# LedDisplay.net
KiCad netlist of a schematic drawn in EAGLE
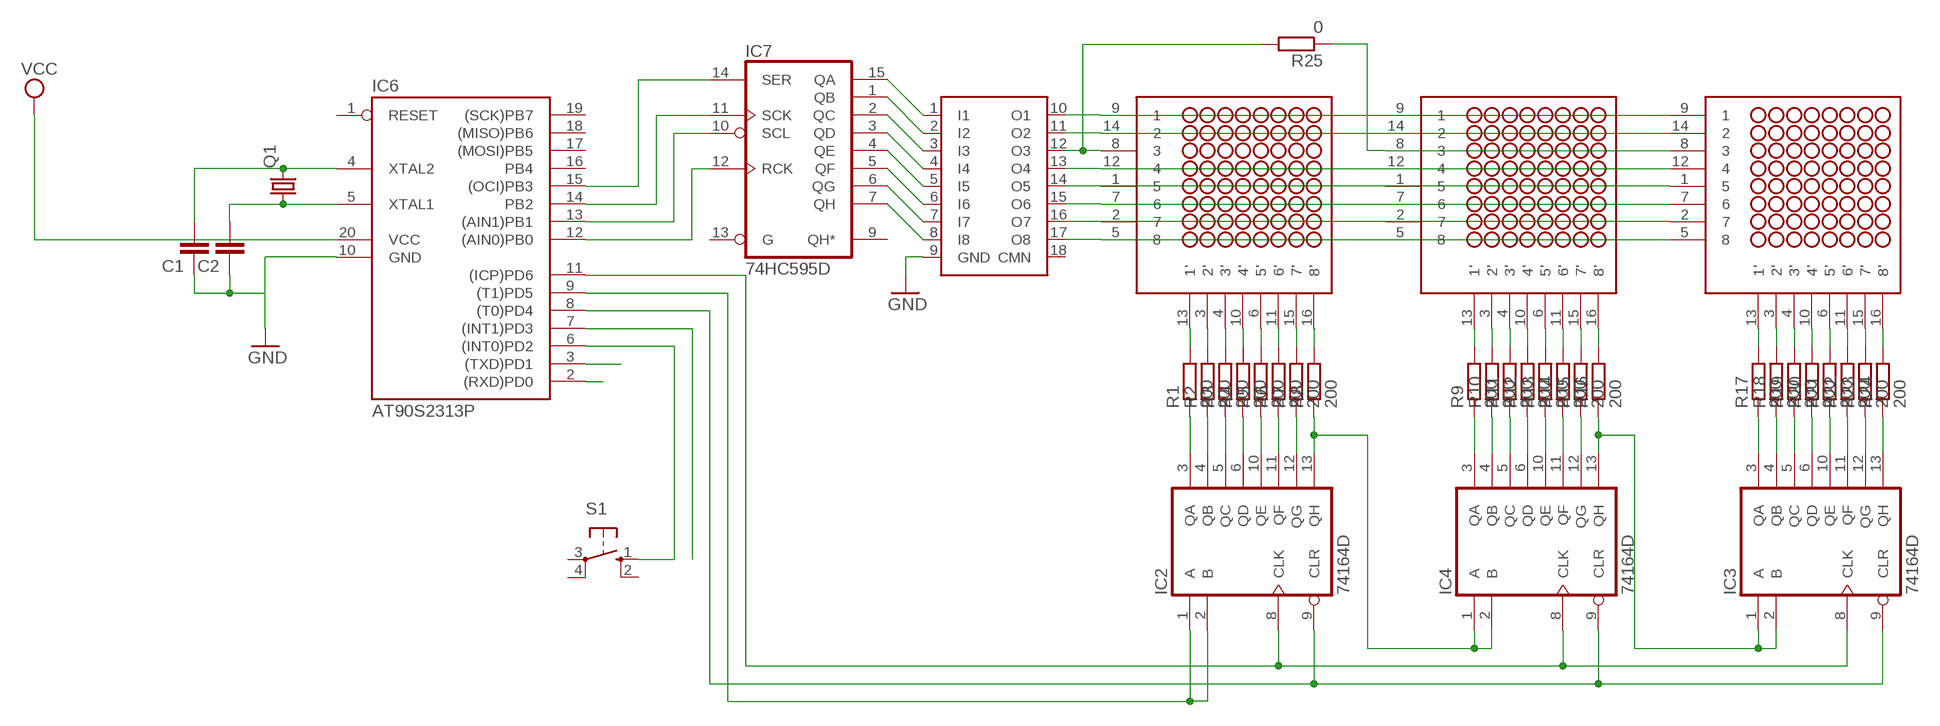
[diagram p0: schematic, sheet 1]

(export (version "E")
  (design (tool "Eeschema 10.0.6"))
  (components
    (comp (ref "C1")
      (value "C2,5-3")
      (footprint "eagle-import:C2.5-3")
      (libsource (lib "eagle-import") (part "C2,5-3"))
    )
    (comp (ref "C2")
      (value "C2,5-3")
      (footprint "eagle-import:C2.5-3")
      (libsource (lib "eagle-import") (part "C2,5-3"))
    )
    (comp (ref "IC2")
      (value "74164D")
      (footprint "eagle-import:SO14")
      (libsource (lib "eagle-import") (part "74164D"))
    )
    (comp (ref "IC3")
      (value "74164D")
      (footprint "eagle-import:SO14")
      (libsource (lib "eagle-import") (part "74164D"))
    )
    (comp (ref "IC4")
      (value "74164D")
      (footprint "eagle-import:SO14")
      (libsource (lib "eagle-import") (part "74164D"))
    )
    (comp (ref "IC6")
      (value "AT90S2313P")
      (footprint "eagle-import:DIL20")
      (libsource (lib "eagle-import") (part "AT90S2313P"))
    )
    (comp (ref "IC7")
      (value "74HC595D")
      (footprint "eagle-import:SO16")
      (libsource (lib "eagle-import") (part "74595DHC"))
    )
    (comp (ref "Q1")
      (value "CRYSTALHC49U70")
      (footprint "eagle-import:HC49U70")
      (libsource (lib "eagle-import") (part "CRYSTALHC49U70"))
    )
    (comp (ref "R1")
      (value "200")
      (footprint "eagle-import:M1206")
      (libsource (lib "eagle-import") (part "R-EU_M1206"))
    )
    (comp (ref "R2")
      (value "200")
      (footprint "eagle-import:M1206")
      (libsource (lib "eagle-import") (part "R-EU_M1206"))
    )
    (comp (ref "R3")
      (value "200")
      (footprint "eagle-import:M1206")
      (libsource (lib "eagle-import") (part "R-EU_M1206"))
    )
    (comp (ref "R4")
      (value "200")
      (footprint "eagle-import:M1206")
      (libsource (lib "eagle-import") (part "R-EU_M1206"))
    )
    (comp (ref "R5")
      (value "200")
      (footprint "eagle-import:M1206")
      (libsource (lib "eagle-import") (part "R-EU_M1206"))
    )
    (comp (ref "R6")
      (value "200")
      (footprint "eagle-import:M1206")
      (libsource (lib "eagle-import") (part "R-EU_M1206"))
    )
    (comp (ref "R7")
      (value "200")
      (footprint "eagle-import:M1206")
      (libsource (lib "eagle-import") (part "R-EU_M1206"))
    )
    (comp (ref "R8")
      (value "200")
      (footprint "eagle-import:M1206")
      (libsource (lib "eagle-import") (part "R-EU_M1206"))
    )
    (comp (ref "R9")
      (value "200")
      (footprint "eagle-import:M1206")
      (libsource (lib "eagle-import") (part "R-EU_M1206"))
    )
    (comp (ref "R10")
      (value "200")
      (footprint "eagle-import:M1206")
      (libsource (lib "eagle-import") (part "R-EU_M1206"))
    )
    (comp (ref "R11")
      (value "200")
      (footprint "eagle-import:M1206")
      (libsource (lib "eagle-import") (part "R-EU_M1206"))
    )
    (comp (ref "R12")
      (value "200")
      (footprint "eagle-import:M1206")
      (libsource (lib "eagle-import") (part "R-EU_M1206"))
    )
    (comp (ref "R13")
      (value "200")
      (footprint "eagle-import:M1206")
      (libsource (lib "eagle-import") (part "R-EU_M1206"))
    )
    (comp (ref "R14")
      (value "200")
      (footprint "eagle-import:M1206")
      (libsource (lib "eagle-import") (part "R-EU_M1206"))
    )
    (comp (ref "R15")
      (value "200")
      (footprint "eagle-import:M1206")
      (libsource (lib "eagle-import") (part "R-EU_M1206"))
    )
    (comp (ref "R16")
      (value "200")
      (footprint "eagle-import:M1206")
      (libsource (lib "eagle-import") (part "R-EU_M1206"))
    )
    (comp (ref "R17")
      (value "200")
      (footprint "eagle-import:M1206")
      (libsource (lib "eagle-import") (part "R-EU_M1206"))
    )
    (comp (ref "R18")
      (value "200")
      (footprint "eagle-import:M1206")
      (libsource (lib "eagle-import") (part "R-EU_M1206"))
    )
    (comp (ref "R19")
      (value "200")
      (footprint "eagle-import:M1206")
      (libsource (lib "eagle-import") (part "R-EU_M1206"))
    )
    (comp (ref "R20")
      (value "200")
      (footprint "eagle-import:M1206")
      (libsource (lib "eagle-import") (part "R-EU_M1206"))
    )
    (comp (ref "R21")
      (value "200")
      (footprint "eagle-import:M1206")
      (libsource (lib "eagle-import") (part "R-EU_M1206"))
    )
    (comp (ref "R22")
      (value "200")
      (footprint "eagle-import:M1206")
      (libsource (lib "eagle-import") (part "R-EU_M1206"))
    )
    (comp (ref "R23")
      (value "200")
      (footprint "eagle-import:M1206")
      (libsource (lib "eagle-import") (part "R-EU_M1206"))
    )
    (comp (ref "R24")
      (value "200")
      (footprint "eagle-import:M1206")
      (libsource (lib "eagle-import") (part "R-EU_M1206"))
    )
    (comp (ref "R25")
      (value "0")
      (footprint "eagle-import:M1206")
      (libsource (lib "eagle-import") (part "R-EU_M1206"))
    )
    (comp (ref "S1")
      (value "10-XX")
      (footprint "eagle-import:B3F-10XX")
      (fields (field (name "MPN") "B3F-1000"))
      (libsource (lib "eagle-import") (part "10-XX"))
    )
    (comp (ref "U$1")
      (value "NFM-12881BG-11")
      (footprint "eagle-import:NFM-12881BG-11")
      (libsource (lib "eagle-import") (part "NFM-12881BG-11"))
    )
    (comp (ref "U$2")
      (value "NFM-12881BG-11")
      (footprint "eagle-import:NFM-12881BG-11")
      (libsource (lib "eagle-import") (part "NFM-12881BG-11"))
    )
    (comp (ref "U$3")
      (value "NFM-12881BG-11")
      (footprint "eagle-import:NFM-12881BG-11")
      (libsource (lib "eagle-import") (part "NFM-12881BG-11"))
    )
    (comp (ref "U$4")
      (value "ULN2803A")
      (footprint "eagle-import:SO18W")
      (libsource (lib "eagle-import") (part "ULN2803A"))
    )
  )
  (nets
    (net (code "1") (name "GND") (class "Default")
      (node (ref "C1") (pin "1") (pinfunction "1_1") (pintype "passive"))
      (node (ref "C2") (pin "1") (pinfunction "1_1") (pintype "passive"))
      (node (ref "IC6") (pin "10") (pinfunction "GND_10") (pintype "power_in"))
      (node (ref "U$4") (pin "9") (pinfunction "GND_9") (pintype "bidirectional"))
    )
    (net (code "2") (name "Net-(IC2A-A)") (class "Default")
      (node (ref "IC2") (pin "1") (pinfunction "A_1") (pintype "input"))
      (node (ref "IC2") (pin "2") (pinfunction "B_2") (pintype "input"))
      (node (ref "IC6") (pin "9") (pinfunction "(T1)PD5_9") (pintype "bidirectional"))
    )
    (net (code "3") (name "Net-(IC2A-CLK)") (class "Default")
      (node (ref "IC2") (pin "8") (pinfunction "CLK_8") (pintype "input"))
      (node (ref "IC3") (pin "8") (pinfunction "CLK_8") (pintype "input"))
      (node (ref "IC4") (pin "8") (pinfunction "CLK_8") (pintype "input"))
      (node (ref "IC6") (pin "11") (pinfunction "(ICP)PD6_11") (pintype "bidirectional"))
    )
    (net (code "4") (name "Net-(IC2A-CLR)") (class "Default")
      (node (ref "IC2") (pin "9") (pinfunction "CLR_9") (pintype "input"))
      (node (ref "IC3") (pin "9") (pinfunction "CLR_9") (pintype "input"))
      (node (ref "IC4") (pin "9") (pinfunction "CLR_9") (pintype "input"))
      (node (ref "IC6") (pin "8") (pinfunction "(T0)PD4_8") (pintype "bidirectional"))
    )
    (net (code "5") (name "Net-(IC2A-QA)") (class "Default")
      (node (ref "IC2") (pin "3") (pinfunction "QA_3") (pintype "output"))
      (node (ref "R1") (pin "1") (pinfunction "1_1") (pintype "passive"))
    )
    (net (code "6") (name "Net-(IC2A-QB)") (class "Default")
      (node (ref "IC2") (pin "4") (pinfunction "QB_4") (pintype "output"))
      (node (ref "R2") (pin "1") (pinfunction "1_1") (pintype "passive"))
    )
    (net (code "7") (name "Net-(IC2A-QC)") (class "Default")
      (node (ref "IC2") (pin "5") (pinfunction "QC_5") (pintype "output"))
      (node (ref "R3") (pin "1") (pinfunction "1_1") (pintype "passive"))
    )
    (net (code "8") (name "Net-(IC2A-QD)") (class "Default")
      (node (ref "IC2") (pin "6") (pinfunction "QD_6") (pintype "output"))
      (node (ref "R4") (pin "1") (pinfunction "1_1") (pintype "passive"))
    )
    (net (code "9") (name "Net-(IC2A-QE)") (class "Default")
      (node (ref "IC2") (pin "10") (pinfunction "QE_10") (pintype "output"))
      (node (ref "R5") (pin "1") (pinfunction "1_1") (pintype "passive"))
    )
    (net (code "10") (name "Net-(IC2A-QF)") (class "Default")
      (node (ref "IC2") (pin "11") (pinfunction "QF_11") (pintype "output"))
      (node (ref "R6") (pin "1") (pinfunction "1_1") (pintype "passive"))
    )
    (net (code "11") (name "Net-(IC2A-QG)") (class "Default")
      (node (ref "IC2") (pin "12") (pinfunction "QG_12") (pintype "output"))
      (node (ref "R7") (pin "1") (pinfunction "1_1") (pintype "passive"))
    )
    (net (code "12") (name "Net-(IC2A-QH)") (class "Default")
      (node (ref "IC2") (pin "13") (pinfunction "QH_13") (pintype "output"))
      (node (ref "IC4") (pin "1") (pinfunction "A_1") (pintype "input"))
      (node (ref "IC4") (pin "2") (pinfunction "B_2") (pintype "input"))
      (node (ref "R8") (pin "1") (pinfunction "1_1") (pintype "passive"))
    )
    (net (code "13") (name "Net-(IC3A-A)") (class "Default")
      (node (ref "IC3") (pin "1") (pinfunction "A_1") (pintype "input"))
      (node (ref "IC3") (pin "2") (pinfunction "B_2") (pintype "input"))
      (node (ref "IC4") (pin "13") (pinfunction "QH_13") (pintype "output"))
      (node (ref "R16") (pin "1") (pinfunction "1_1") (pintype "passive"))
    )
    (net (code "14") (name "Net-(IC3A-QA)") (class "Default")
      (node (ref "IC3") (pin "3") (pinfunction "QA_3") (pintype "output"))
      (node (ref "R17") (pin "1") (pinfunction "1_1") (pintype "passive"))
    )
    (net (code "15") (name "Net-(IC3A-QB)") (class "Default")
      (node (ref "IC3") (pin "4") (pinfunction "QB_4") (pintype "output"))
      (node (ref "R18") (pin "1") (pinfunction "1_1") (pintype "passive"))
    )
    (net (code "16") (name "Net-(IC3A-QC)") (class "Default")
      (node (ref "IC3") (pin "5") (pinfunction "QC_5") (pintype "output"))
      (node (ref "R19") (pin "1") (pinfunction "1_1") (pintype "passive"))
    )
    (net (code "17") (name "Net-(IC3A-QD)") (class "Default")
      (node (ref "IC3") (pin "6") (pinfunction "QD_6") (pintype "output"))
      (node (ref "R20") (pin "1") (pinfunction "1_1") (pintype "passive"))
    )
    (net (code "18") (name "Net-(IC3A-QE)") (class "Default")
      (node (ref "IC3") (pin "10") (pinfunction "QE_10") (pintype "output"))
      (node (ref "R21") (pin "1") (pinfunction "1_1") (pintype "passive"))
    )
    (net (code "19") (name "Net-(IC3A-QF)") (class "Default")
      (node (ref "IC3") (pin "11") (pinfunction "QF_11") (pintype "output"))
      (node (ref "R22") (pin "1") (pinfunction "1_1") (pintype "passive"))
    )
    (net (code "20") (name "Net-(IC3A-QG)") (class "Default")
      (node (ref "IC3") (pin "12") (pinfunction "QG_12") (pintype "output"))
      (node (ref "R23") (pin "1") (pinfunction "1_1") (pintype "passive"))
    )
    (net (code "21") (name "Net-(IC3A-QH)") (class "Default")
      (node (ref "IC3") (pin "13") (pinfunction "QH_13") (pintype "output"))
      (node (ref "R24") (pin "1") (pinfunction "1_1") (pintype "passive"))
    )
    (net (code "22") (name "Net-(IC4A-QA)") (class "Default")
      (node (ref "IC4") (pin "3") (pinfunction "QA_3") (pintype "output"))
      (node (ref "R9") (pin "1") (pinfunction "1_1") (pintype "passive"))
    )
    (net (code "23") (name "Net-(IC4A-QB)") (class "Default")
      (node (ref "IC4") (pin "4") (pinfunction "QB_4") (pintype "output"))
      (node (ref "R10") (pin "1") (pinfunction "1_1") (pintype "passive"))
    )
    (net (code "24") (name "Net-(IC4A-QC)") (class "Default")
      (node (ref "IC4") (pin "5") (pinfunction "QC_5") (pintype "output"))
      (node (ref "R11") (pin "1") (pinfunction "1_1") (pintype "passive"))
    )
    (net (code "25") (name "Net-(IC4A-QD)") (class "Default")
      (node (ref "IC4") (pin "6") (pinfunction "QD_6") (pintype "output"))
      (node (ref "R12") (pin "1") (pinfunction "1_1") (pintype "passive"))
    )
    (net (code "26") (name "Net-(IC4A-QE)") (class "Default")
      (node (ref "IC4") (pin "10") (pinfunction "QE_10") (pintype "output"))
      (node (ref "R13") (pin "1") (pinfunction "1_1") (pintype "passive"))
    )
    (net (code "27") (name "Net-(IC4A-QF)") (class "Default")
      (node (ref "IC4") (pin "11") (pinfunction "QF_11") (pintype "output"))
      (node (ref "R14") (pin "1") (pinfunction "1_1") (pintype "passive"))
    )
    (net (code "28") (name "Net-(IC4A-QG)") (class "Default")
      (node (ref "IC4") (pin "12") (pinfunction "QG_12") (pintype "output"))
      (node (ref "R15") (pin "1") (pinfunction "1_1") (pintype "passive"))
    )
    (net (code "29") (name "Net-(IC6-(AIN0)PB0)") (class "Default")
      (node (ref "IC6") (pin "12") (pinfunction "(AIN0)PB0_12") (pintype "bidirectional"))
      (node (ref "IC7") (pin "12") (pinfunction "RCK_12") (pintype "input"))
    )
    (net (code "30") (name "Net-(IC6-(AIN1)PB1)") (class "Default")
      (node (ref "IC6") (pin "13") (pinfunction "(AIN1)PB1_13") (pintype "bidirectional"))
      (node (ref "IC7") (pin "10") (pinfunction "SCL_10") (pintype "input"))
    )
    (net (code "31") (name "Net-(IC6-(INT0)PD2)") (class "Default")
      (node (ref "IC6") (pin "6") (pinfunction "(INT0)PD2_6") (pintype "bidirectional"))
      (node (ref "S1") (pin "1") (pinfunction "S_1") (pintype "passive"))
    )
    (net (code "32") (name "Net-(IC6-(OCI)PB3)") (class "Default")
      (node (ref "IC6") (pin "15") (pinfunction "(OCI)PB3_15") (pintype "bidirectional"))
      (node (ref "IC7") (pin "14") (pinfunction "SER_14") (pintype "input"))
    )
    (net (code "33") (name "Net-(IC6-PB2)") (class "Default")
      (node (ref "IC6") (pin "14") (pinfunction "PB2_14") (pintype "bidirectional"))
      (node (ref "IC7") (pin "11") (pinfunction "SCK_11") (pintype "input"))
    )
    (net (code "34") (name "Net-(IC6-XTAL1)") (class "Default")
      (node (ref "C2") (pin "2") (pinfunction "2_2") (pintype "passive"))
      (node (ref "IC6") (pin "5") (pinfunction "XTAL1_5") (pintype "bidirectional"))
      (node (ref "Q1") (pin "1") (pinfunction "1_1") (pintype "passive"))
    )
    (net (code "35") (name "Net-(IC6-XTAL2)") (class "Default")
      (node (ref "C1") (pin "2") (pinfunction "2_2") (pintype "passive"))
      (node (ref "IC6") (pin "4") (pinfunction "XTAL2_4") (pintype "bidirectional"))
      (node (ref "Q1") (pin "2") (pinfunction "2_2") (pintype "passive"))
    )
    (net (code "36") (name "Net-(IC7A-QA)") (class "Default")
      (node (ref "IC7") (pin "15") (pinfunction "QA_15") (pintype "tri_state"))
      (node (ref "U$4") (pin "1") (pinfunction "I1_1") (pintype "bidirectional"))
    )
    (net (code "37") (name "Net-(IC7A-QB)") (class "Default")
      (node (ref "IC7") (pin "1") (pinfunction "QB_1") (pintype "tri_state"))
      (node (ref "U$4") (pin "2") (pinfunction "I2_2") (pintype "bidirectional"))
    )
    (net (code "38") (name "Net-(IC7A-QC)") (class "Default")
      (node (ref "IC7") (pin "2") (pinfunction "QC_2") (pintype "tri_state"))
      (node (ref "U$4") (pin "3") (pinfunction "I3_3") (pintype "bidirectional"))
    )
    (net (code "39") (name "Net-(IC7A-QD)") (class "Default")
      (node (ref "IC7") (pin "3") (pinfunction "QD_3") (pintype "tri_state"))
      (node (ref "U$4") (pin "4") (pinfunction "I4_4") (pintype "bidirectional"))
    )
    (net (code "40") (name "Net-(IC7A-QE)") (class "Default")
      (node (ref "IC7") (pin "4") (pinfunction "QE_4") (pintype "tri_state"))
      (node (ref "U$4") (pin "5") (pinfunction "I5_5") (pintype "bidirectional"))
    )
    (net (code "41") (name "Net-(IC7A-QF)") (class "Default")
      (node (ref "IC7") (pin "5") (pinfunction "QF_5") (pintype "tri_state"))
      (node (ref "U$4") (pin "6") (pinfunction "I6_6") (pintype "bidirectional"))
    )
    (net (code "42") (name "Net-(IC7A-QG)") (class "Default")
      (node (ref "IC7") (pin "6") (pinfunction "QG_6") (pintype "tri_state"))
      (node (ref "U$4") (pin "7") (pinfunction "I7_7") (pintype "bidirectional"))
    )
    (net (code "43") (name "Net-(IC7A-QH)") (class "Default")
      (node (ref "IC7") (pin "7") (pinfunction "QH_7") (pintype "tri_state"))
      (node (ref "U$4") (pin "8") (pinfunction "I8_8") (pintype "bidirectional"))
    )
    (net (code "44") (name "Net-(U$1-1')") (class "Default")
      (node (ref "R1") (pin "2") (pinfunction "2_2") (pintype "passive"))
      (node (ref "U$1") (pin "13") (pinfunction "1'_13") (pintype "output"))
    )
    (net (code "45") (name "Net-(U$1-1)") (class "Default")
      (node (ref "U$1") (pin "9") (pinfunction "1_9") (pintype "input"))
      (node (ref "U$2") (pin "9") (pinfunction "1_9") (pintype "input"))
      (node (ref "U$3") (pin "9") (pinfunction "1_9") (pintype "input"))
      (node (ref "U$4") (pin "10") (pinfunction "O1_10") (pintype "bidirectional"))
    )
    (net (code "46") (name "Net-(U$1-2')") (class "Default")
      (node (ref "R2") (pin "2") (pinfunction "2_2") (pintype "passive"))
      (node (ref "U$1") (pin "3") (pinfunction "2'_3") (pintype "output"))
    )
    (net (code "47") (name "Net-(U$1-2)") (class "Default")
      (node (ref "U$1") (pin "14") (pinfunction "2_14") (pintype "input"))
      (node (ref "U$2") (pin "14") (pinfunction "2_14") (pintype "input"))
      (node (ref "U$3") (pin "14") (pinfunction "2_14") (pintype "input"))
      (node (ref "U$4") (pin "11") (pinfunction "O2_11") (pintype "bidirectional"))
    )
    (net (code "48") (name "Net-(U$1-3')") (class "Default")
      (node (ref "R3") (pin "2") (pinfunction "2_2") (pintype "passive"))
      (node (ref "U$1") (pin "4") (pinfunction "3'_4") (pintype "output"))
    )
    (net (code "49") (name "Net-(U$1-3)") (class "Default")
      (node (ref "R25") (pin "2") (pinfunction "2_2") (pintype "passive"))
      (node (ref "U$1") (pin "8") (pinfunction "3_8") (pintype "input"))
      (node (ref "U$4") (pin "12") (pinfunction "O3_12") (pintype "bidirectional"))
    )
    (net (code "50") (name "Net-(U$1-4')") (class "Default")
      (node (ref "R4") (pin "2") (pinfunction "2_2") (pintype "passive"))
      (node (ref "U$1") (pin "10") (pinfunction "4'_10") (pintype "output"))
    )
    (net (code "51") (name "Net-(U$1-4)") (class "Default")
      (node (ref "U$1") (pin "12") (pinfunction "4_12") (pintype "input"))
      (node (ref "U$2") (pin "12") (pinfunction "4_12") (pintype "input"))
      (node (ref "U$3") (pin "12") (pinfunction "4_12") (pintype "input"))
      (node (ref "U$4") (pin "13") (pinfunction "O4_13") (pintype "bidirectional"))
    )
    (net (code "52") (name "Net-(U$1-5')") (class "Default")
      (node (ref "R5") (pin "2") (pinfunction "2_2") (pintype "passive"))
      (node (ref "U$1") (pin "6") (pinfunction "5'_6") (pintype "output"))
    )
    (net (code "53") (name "Net-(U$1-5)") (class "Default")
      (node (ref "U$1") (pin "1") (pinfunction "5_1") (pintype "input"))
      (node (ref "U$2") (pin "1") (pinfunction "5_1") (pintype "input"))
      (node (ref "U$3") (pin "1") (pinfunction "5_1") (pintype "input"))
      (node (ref "U$4") (pin "14") (pinfunction "O5_14") (pintype "bidirectional"))
    )
    (net (code "54") (name "Net-(U$1-6')") (class "Default")
      (node (ref "R6") (pin "2") (pinfunction "2_2") (pintype "passive"))
      (node (ref "U$1") (pin "11") (pinfunction "6'_11") (pintype "output"))
    )
    (net (code "55") (name "Net-(U$1-6)") (class "Default")
      (node (ref "U$1") (pin "7") (pinfunction "6_7") (pintype "input"))
      (node (ref "U$2") (pin "7") (pinfunction "6_7") (pintype "input"))
      (node (ref "U$3") (pin "7") (pinfunction "6_7") (pintype "input"))
      (node (ref "U$4") (pin "15") (pinfunction "O6_15") (pintype "bidirectional"))
    )
    (net (code "56") (name "Net-(U$1-7')") (class "Default")
      (node (ref "R7") (pin "2") (pinfunction "2_2") (pintype "passive"))
      (node (ref "U$1") (pin "15") (pinfunction "7'_15") (pintype "output"))
    )
    (net (code "57") (name "Net-(U$1-7)") (class "Default")
      (node (ref "U$1") (pin "2") (pinfunction "7_2") (pintype "input"))
      (node (ref "U$2") (pin "2") (pinfunction "7_2") (pintype "input"))
      (node (ref "U$3") (pin "2") (pinfunction "7_2") (pintype "input"))
      (node (ref "U$4") (pin "16") (pinfunction "O7_16") (pintype "bidirectional"))
    )
    (net (code "58") (name "Net-(U$1-8')") (class "Default")
      (node (ref "R8") (pin "2") (pinfunction "2_2") (pintype "passive"))
      (node (ref "U$1") (pin "16") (pinfunction "8'_16") (pintype "output"))
    )
    (net (code "59") (name "Net-(U$1-8)") (class "Default")
      (node (ref "U$1") (pin "5") (pinfunction "8_5") (pintype "input"))
      (node (ref "U$2") (pin "5") (pinfunction "8_5") (pintype "input"))
      (node (ref "U$3") (pin "5") (pinfunction "8_5") (pintype "input"))
      (node (ref "U$4") (pin "17") (pinfunction "O8_17") (pintype "bidirectional"))
    )
    (net (code "60") (name "Net-(U$2-1')") (class "Default")
      (node (ref "R9") (pin "2") (pinfunction "2_2") (pintype "passive"))
      (node (ref "U$2") (pin "13") (pinfunction "1'_13") (pintype "output"))
    )
    (net (code "61") (name "Net-(U$2-2')") (class "Default")
      (node (ref "R10") (pin "2") (pinfunction "2_2") (pintype "passive"))
      (node (ref "U$2") (pin "3") (pinfunction "2'_3") (pintype "output"))
    )
    (net (code "62") (name "Net-(U$2-3')") (class "Default")
      (node (ref "R11") (pin "2") (pinfunction "2_2") (pintype "passive"))
      (node (ref "U$2") (pin "4") (pinfunction "3'_4") (pintype "output"))
    )
    (net (code "63") (name "Net-(U$2-3)") (class "Default")
      (node (ref "R25") (pin "1") (pinfunction "1_1") (pintype "passive"))
      (node (ref "U$2") (pin "8") (pinfunction "3_8") (pintype "input"))
      (node (ref "U$3") (pin "8") (pinfunction "3_8") (pintype "input"))
    )
    (net (code "64") (name "Net-(U$2-4')") (class "Default")
      (node (ref "R12") (pin "2") (pinfunction "2_2") (pintype "passive"))
      (node (ref "U$2") (pin "10") (pinfunction "4'_10") (pintype "output"))
    )
    (net (code "65") (name "Net-(U$2-5')") (class "Default")
      (node (ref "R13") (pin "2") (pinfunction "2_2") (pintype "passive"))
      (node (ref "U$2") (pin "6") (pinfunction "5'_6") (pintype "output"))
    )
    (net (code "66") (name "Net-(U$2-6')") (class "Default")
      (node (ref "R14") (pin "2") (pinfunction "2_2") (pintype "passive"))
      (node (ref "U$2") (pin "11") (pinfunction "6'_11") (pintype "output"))
    )
    (net (code "67") (name "Net-(U$2-7')") (class "Default")
      (node (ref "R15") (pin "2") (pinfunction "2_2") (pintype "passive"))
      (node (ref "U$2") (pin "15") (pinfunction "7'_15") (pintype "output"))
    )
    (net (code "68") (name "Net-(U$2-8')") (class "Default")
      (node (ref "R16") (pin "2") (pinfunction "2_2") (pintype "passive"))
      (node (ref "U$2") (pin "16") (pinfunction "8'_16") (pintype "output"))
    )
    (net (code "69") (name "Net-(U$3-1')") (class "Default")
      (node (ref "R17") (pin "2") (pinfunction "2_2") (pintype "passive"))
      (node (ref "U$3") (pin "13") (pinfunction "1'_13") (pintype "output"))
    )
    (net (code "70") (name "Net-(U$3-2')") (class "Default")
      (node (ref "R18") (pin "2") (pinfunction "2_2") (pintype "passive"))
      (node (ref "U$3") (pin "3") (pinfunction "2'_3") (pintype "output"))
    )
    (net (code "71") (name "Net-(U$3-3')") (class "Default")
      (node (ref "R19") (pin "2") (pinfunction "2_2") (pintype "passive"))
      (node (ref "U$3") (pin "4") (pinfunction "3'_4") (pintype "output"))
    )
    (net (code "72") (name "Net-(U$3-4')") (class "Default")
      (node (ref "R20") (pin "2") (pinfunction "2_2") (pintype "passive"))
      (node (ref "U$3") (pin "10") (pinfunction "4'_10") (pintype "output"))
    )
    (net (code "73") (name "Net-(U$3-5')") (class "Default")
      (node (ref "R21") (pin "2") (pinfunction "2_2") (pintype "passive"))
      (node (ref "U$3") (pin "6") (pinfunction "5'_6") (pintype "output"))
    )
    (net (code "74") (name "Net-(U$3-6')") (class "Default")
      (node (ref "R22") (pin "2") (pinfunction "2_2") (pintype "passive"))
      (node (ref "U$3") (pin "11") (pinfunction "6'_11") (pintype "output"))
    )
    (net (code "75") (name "Net-(U$3-7')") (class "Default")
      (node (ref "R23") (pin "2") (pinfunction "2_2") (pintype "passive"))
      (node (ref "U$3") (pin "15") (pinfunction "7'_15") (pintype "output"))
    )
    (net (code "76") (name "Net-(U$3-8')") (class "Default")
      (node (ref "R24") (pin "2") (pinfunction "2_2") (pintype "passive"))
      (node (ref "U$3") (pin "16") (pinfunction "8'_16") (pintype "output"))
    )
    (net (code "77") (name "VCC") (class "Default")
      (node (ref "IC6") (pin "20") (pinfunction "VCC_20") (pintype "power_in"))
    )
    (net (code "78") (name "unconnected-(IC6-(INT1)PD3-Pad7)") (class "Default")
      (node (ref "IC6") (pin "7") (pinfunction "(INT1)PD3_7") (pintype "bidirectional"))
    )
    (net (code "79") (name "unconnected-(IC6-(MISO)PB6-Pad18)") (class "Default")
      (node (ref "IC6") (pin "18") (pinfunction "(MISO)PB6_18") (pintype "bidirectional"))
    )
    (net (code "80") (name "unconnected-(IC6-(MOSI)PB5-Pad17)") (class "Default")
      (node (ref "IC6") (pin "17") (pinfunction "(MOSI)PB5_17") (pintype "bidirectional"))
    )
    (net (code "81") (name "unconnected-(IC6-(RXD)PD0-Pad2)") (class "Default")
      (node (ref "IC6") (pin "2") (pinfunction "(RXD)PD0_2") (pintype "bidirectional"))
    )
    (net (code "82") (name "unconnected-(IC6-(SCK)PB7-Pad19)") (class "Default")
      (node (ref "IC6") (pin "19") (pinfunction "(SCK)PB7_19") (pintype "bidirectional"))
    )
    (net (code "83") (name "unconnected-(IC6-(TXD)PD1-Pad3)") (class "Default")
      (node (ref "IC6") (pin "3") (pinfunction "(TXD)PD1_3") (pintype "bidirectional"))
    )
    (net (code "84") (name "unconnected-(IC6-PB4-Pad16)") (class "Default")
      (node (ref "IC6") (pin "16") (pinfunction "PB4_16") (pintype "bidirectional"))
    )
    (net (code "85") (name "unconnected-(IC6-RESET-Pad1)") (class "Default")
      (node (ref "IC6") (pin "1") (pinfunction "RESET_1") (pintype "bidirectional"))
    )
    (net (code "86") (name "unconnected-(IC7A-G-Pad13)") (class "Default")
      (node (ref "IC7") (pin "13") (pinfunction "G_13") (pintype "input"))
    )
    (net (code "87") (name "unconnected-(IC7A-QH*-Pad9)") (class "Default")
      (node (ref "IC7") (pin "9") (pinfunction "QH*_9") (pintype "tri_state"))
    )
    (net (code "88") (name "unconnected-(S1-P-Pad3)") (class "Default")
      (node (ref "S1") (pin "3") (pinfunction "P_3") (pintype "passive"))
    )
    (net (code "89") (name "unconnected-(S1-P1-Pad4)") (class "Default")
      (node (ref "S1") (pin "4") (pinfunction "P1_4") (pintype "passive"))
    )
    (net (code "90") (name "unconnected-(S1-S1-Pad2)") (class "Default")
      (node (ref "S1") (pin "2") (pinfunction "S1_2") (pintype "passive"))
    )
    (net (code "91") (name "unconnected-(U$4-CMN-Pad18)") (class "Default")
      (node (ref "U$4") (pin "18") (pinfunction "CMN_18") (pintype "bidirectional"))
    )
  )
)
